# Fuse_protector.net
KiCad netlist of a schematic drawn in EAGLE
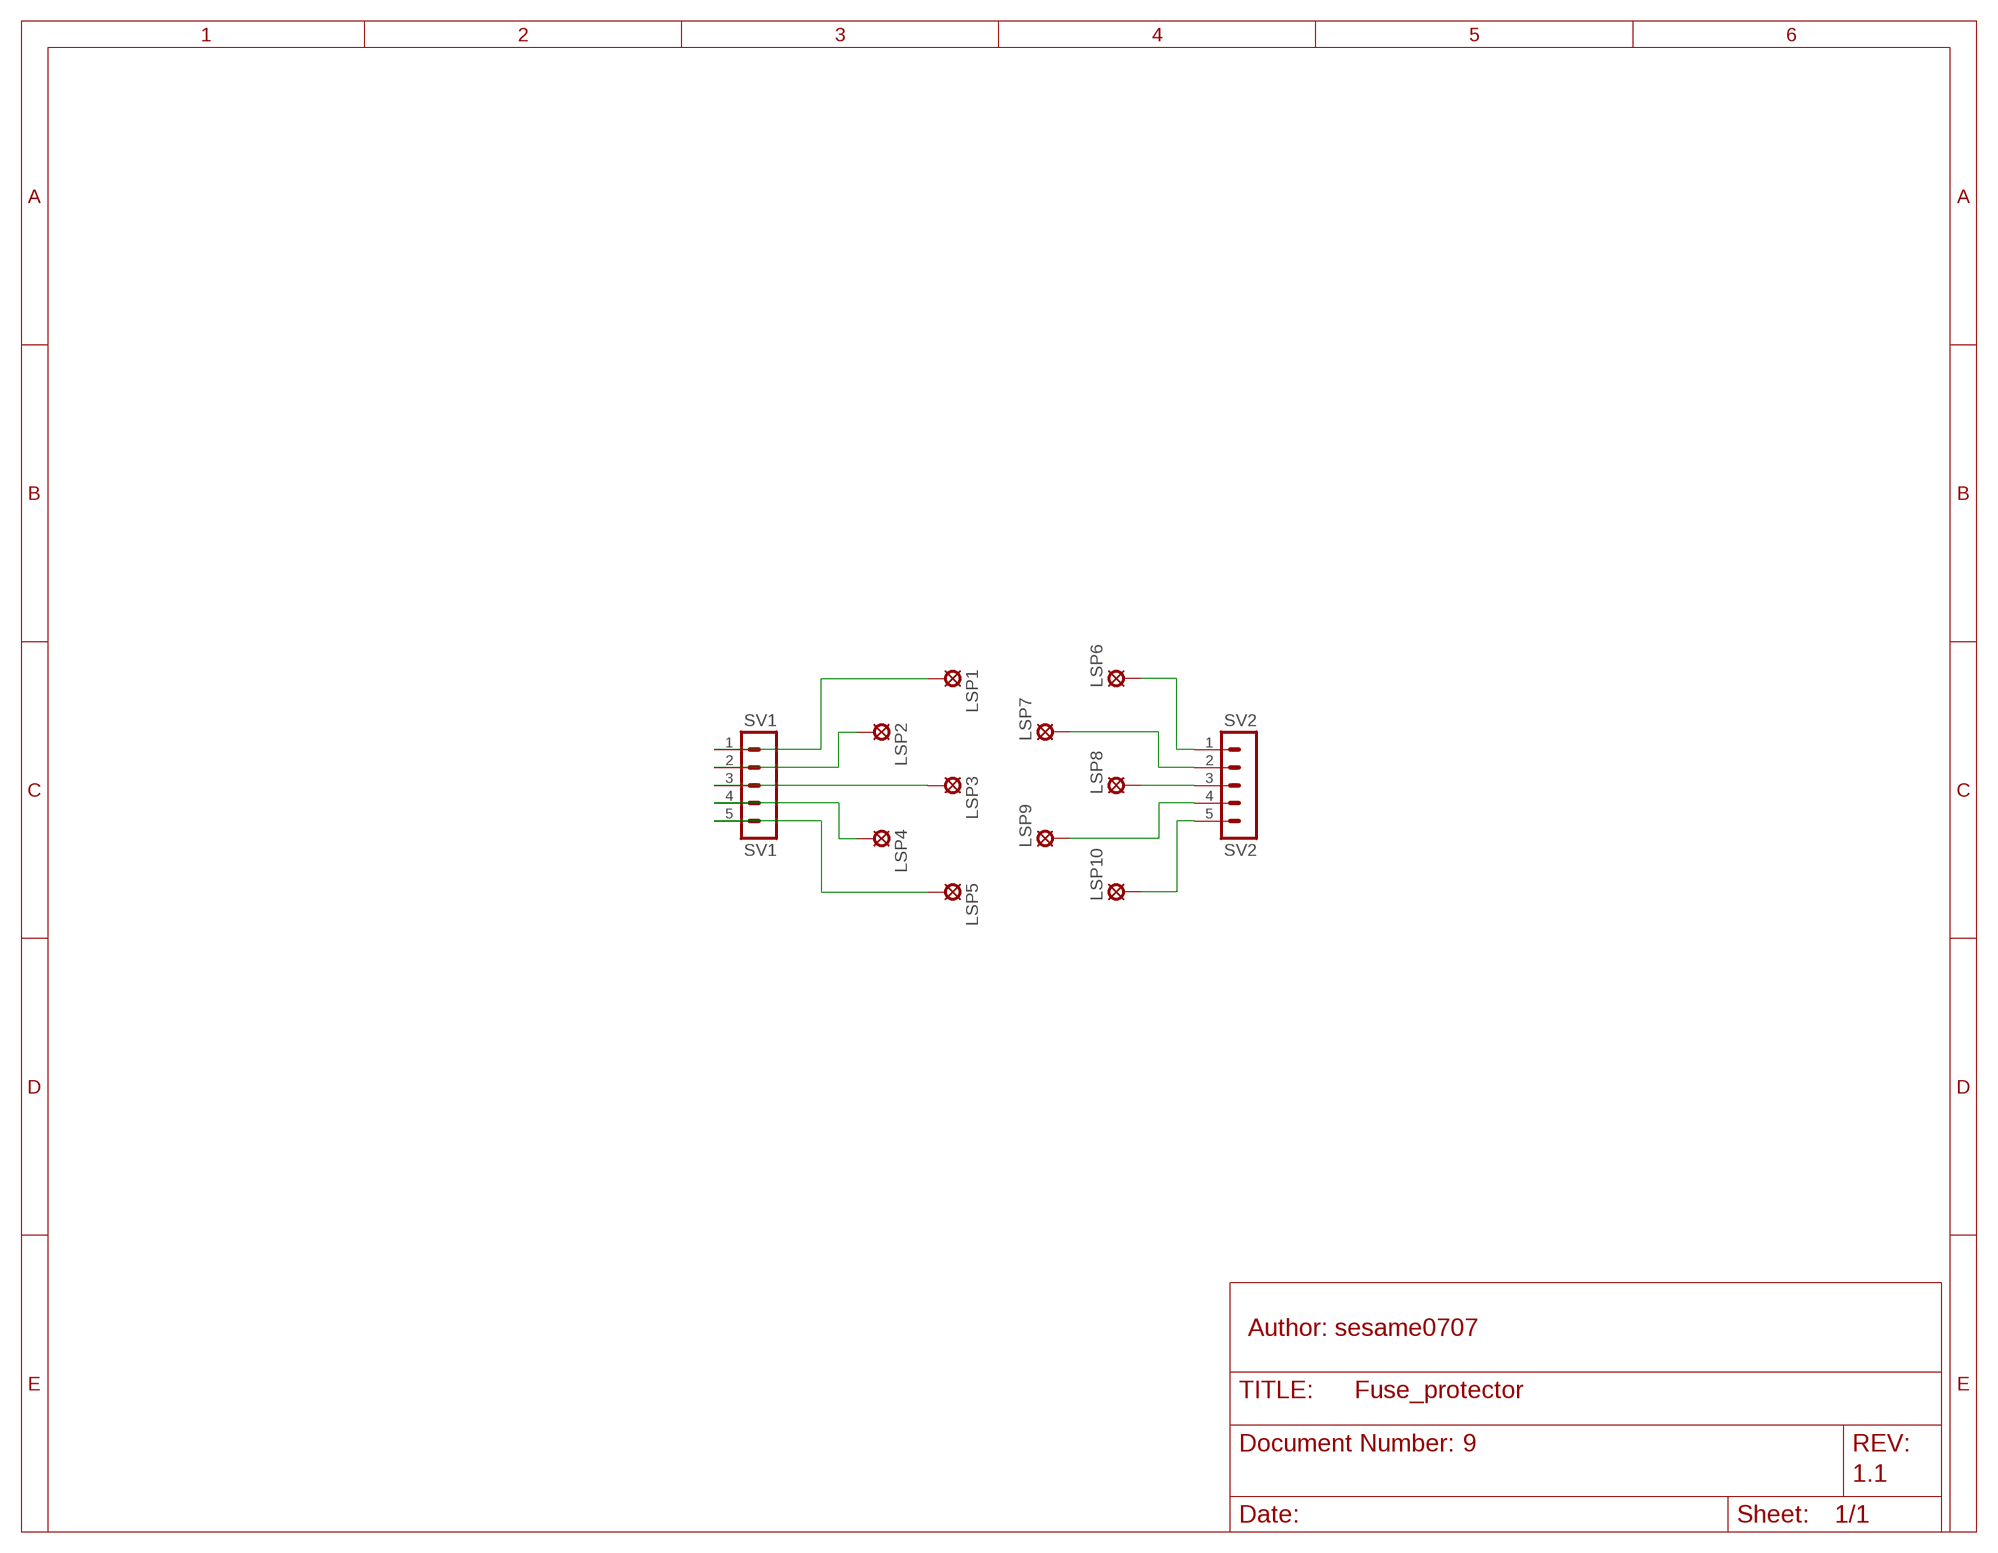
[diagram p0: schematic, sheet 1]

(export (version "E")
  (design (tool "Eeschema 10.0.6"))
  (components
    (comp (ref "LSP1")
      (value "SE14")
      (footprint "eagle-import:SE14")
      (libsource (lib "eagle-import") (part "SE14"))
    )
    (comp (ref "LSP2")
      (value "SE14")
      (footprint "eagle-import:SE14")
      (libsource (lib "eagle-import") (part "SE14"))
    )
    (comp (ref "LSP3")
      (value "SE14")
      (footprint "eagle-import:SE14")
      (libsource (lib "eagle-import") (part "SE14"))
    )
    (comp (ref "LSP4")
      (value "SE14")
      (footprint "eagle-import:SE14")
      (libsource (lib "eagle-import") (part "SE14"))
    )
    (comp (ref "LSP5")
      (value "SE14")
      (footprint "eagle-import:SE14")
      (libsource (lib "eagle-import") (part "SE14"))
    )
    (comp (ref "LSP6")
      (value "SE14")
      (footprint "eagle-import:SE14")
      (libsource (lib "eagle-import") (part "SE14"))
    )
    (comp (ref "LSP7")
      (value "SE14")
      (footprint "eagle-import:SE14")
      (libsource (lib "eagle-import") (part "SE14"))
    )
    (comp (ref "LSP8")
      (value "SE14")
      (footprint "eagle-import:SE14")
      (libsource (lib "eagle-import") (part "SE14"))
    )
    (comp (ref "LSP9")
      (value "SE14")
      (footprint "eagle-import:SE14")
      (libsource (lib "eagle-import") (part "SE14"))
    )
    (comp (ref "LSP10")
      (value "SE14")
      (footprint "eagle-import:SE14")
      (libsource (lib "eagle-import") (part "SE14"))
    )
    (comp (ref "SV1")
      (value "SV1")
      (footprint "eagle-import:MA05-1")
      (libsource (lib "eagle-import") (part "MA05-1"))
    )
    (comp (ref "SV2")
      (value "SV2")
      (footprint "eagle-import:MA05-1")
      (libsource (lib "eagle-import") (part "MA05-1"))
    )
  )
  (nets
    (net (code "1") (name "Net-(LSP1-PadMP)") (class "Default")
      (node (ref "LSP1") (pin "MP") (pinfunction "MP_MP") (pintype "passive"))
      (node (ref "SV1") (pin "1") (pinfunction "1_1") (pintype "passive"))
    )
    (net (code "2") (name "Net-(LSP2-PadMP)") (class "Default")
      (node (ref "LSP2") (pin "MP") (pinfunction "MP_MP") (pintype "passive"))
      (node (ref "SV1") (pin "2") (pinfunction "2_2") (pintype "passive"))
    )
    (net (code "3") (name "Net-(LSP3-PadMP)") (class "Default")
      (node (ref "LSP3") (pin "MP") (pinfunction "MP_MP") (pintype "passive"))
      (node (ref "SV1") (pin "3") (pinfunction "3_3") (pintype "passive"))
    )
    (net (code "4") (name "Net-(LSP4-PadMP)") (class "Default")
      (node (ref "LSP4") (pin "MP") (pinfunction "MP_MP") (pintype "passive"))
      (node (ref "SV1") (pin "4") (pinfunction "4_4") (pintype "passive"))
    )
    (net (code "5") (name "Net-(LSP5-PadMP)") (class "Default")
      (node (ref "LSP5") (pin "MP") (pinfunction "MP_MP") (pintype "passive"))
      (node (ref "SV1") (pin "5") (pinfunction "5_5") (pintype "passive"))
    )
    (net (code "6") (name "Net-(LSP6-PadMP)") (class "Default")
      (node (ref "LSP6") (pin "MP") (pinfunction "MP_MP") (pintype "passive"))
      (node (ref "SV2") (pin "1") (pinfunction "1_1") (pintype "passive"))
    )
    (net (code "7") (name "Net-(LSP7-PadMP)") (class "Default")
      (node (ref "LSP7") (pin "MP") (pinfunction "MP_MP") (pintype "passive"))
      (node (ref "SV2") (pin "2") (pinfunction "2_2") (pintype "passive"))
    )
    (net (code "8") (name "Net-(LSP8-PadMP)") (class "Default")
      (node (ref "LSP8") (pin "MP") (pinfunction "MP_MP") (pintype "passive"))
      (node (ref "SV2") (pin "3") (pinfunction "3_3") (pintype "passive"))
    )
    (net (code "9") (name "Net-(LSP9-PadMP)") (class "Default")
      (node (ref "LSP9") (pin "MP") (pinfunction "MP_MP") (pintype "passive"))
      (node (ref "SV2") (pin "4") (pinfunction "4_4") (pintype "passive"))
    )
    (net (code "10") (name "Net-(LSP10-PadMP)") (class "Default")
      (node (ref "LSP10") (pin "MP") (pinfunction "MP_MP") (pintype "passive"))
      (node (ref "SV2") (pin "5") (pinfunction "5_5") (pintype "passive"))
    )
  )
)
